# SH4_-_OPAMPS.net
KiCad netlist of a schematic drawn in Altium Designer
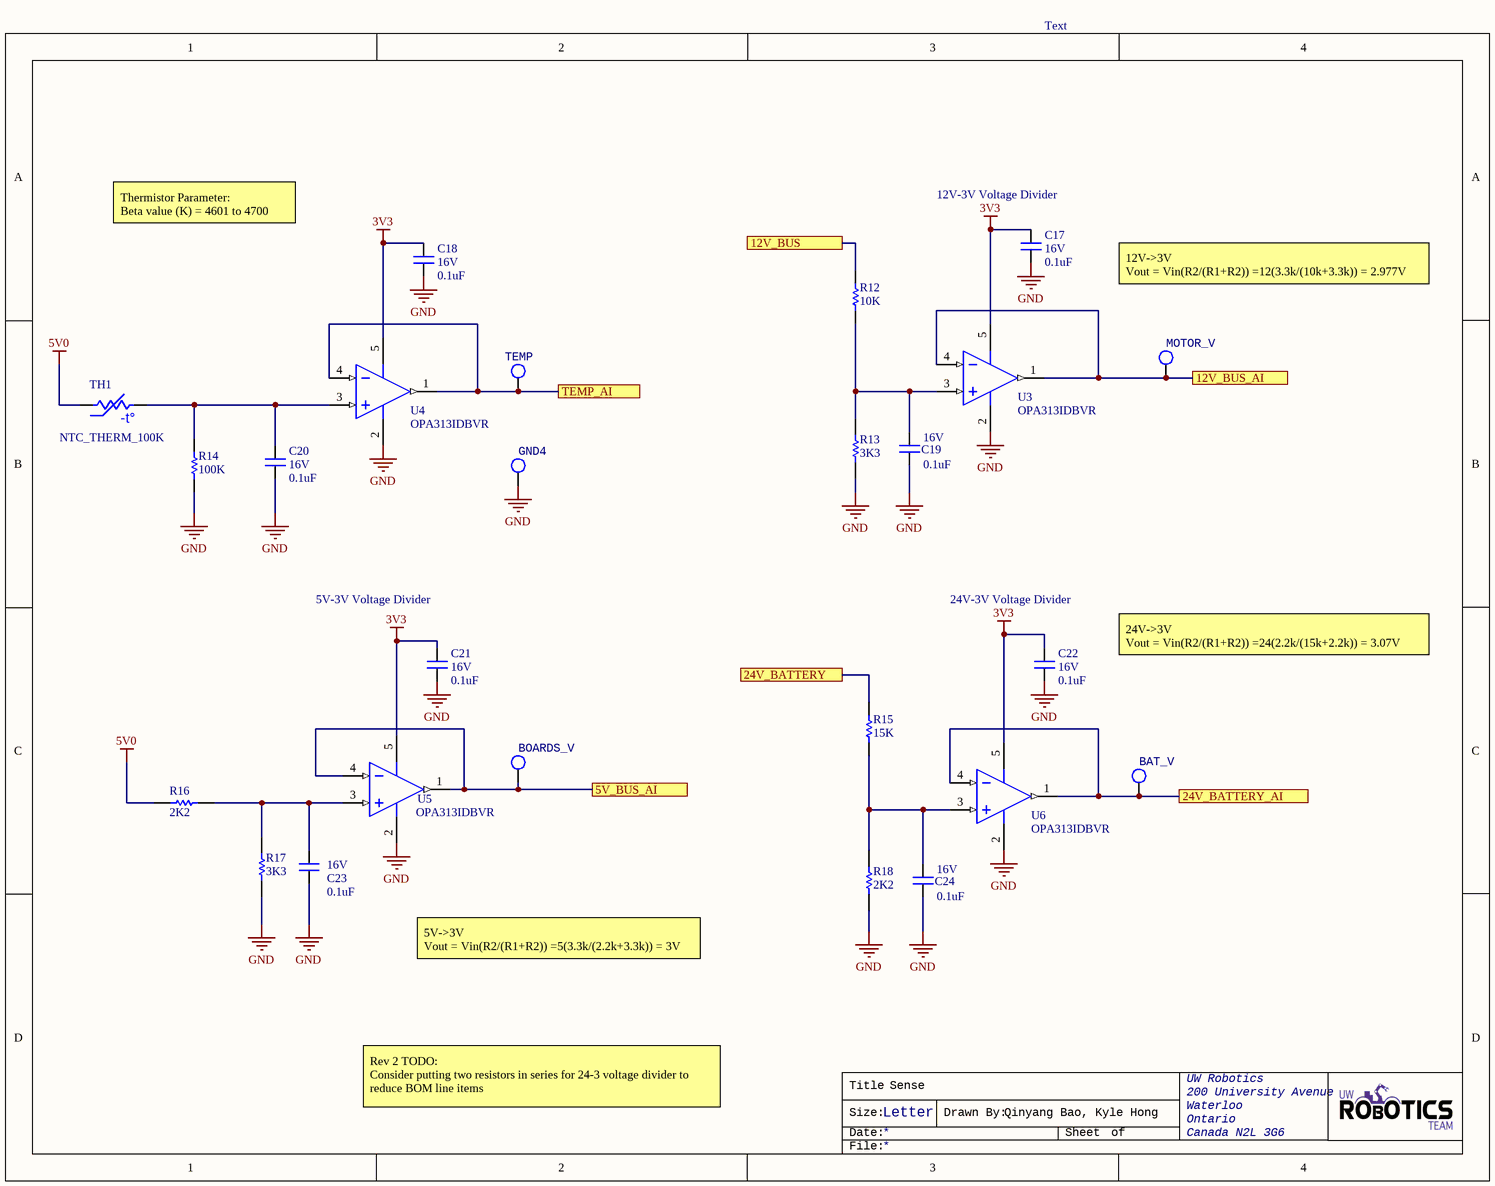
[diagram p0: SH4 - OPAMPS.SchDoc]

(export (version "E")
  (design (tool "Eeschema 10.0.6"))
  (components
    (comp (ref "BAT_V")
      (value "TESTPOINT_LOOP")
      (footprint "TESTPOINT_LOOP")
      (description "Loop testpoint through-hole pad")
      (fields (field (name "MANUFACTURER") "Keystone Electronics"))
      (libsource (lib "UWRT_Schematic_Library_2020") (part "TESTPOINT_LOOP"))
    )
    (comp (ref "BOARDS_V")
      (value "TESTPOINT_LOOP")
      (footprint "TESTPOINT_LOOP")
      (description "Loop testpoint through-hole pad")
      (fields (field (name "MANUFACTURER") "Keystone Electronics"))
      (libsource (lib "UWRT_Schematic_Library_2020") (part "TESTPOINT_LOOP"))
    )
    (comp (ref "C17")
      (value "0.1uF")
      (footprint "CAPC0603(1608)55_N")
      (description "CAP CER 0.1UF 16V X7R 0603")
      (fields
        (field (name "MPN") "CC0603KRX7R7BB104")
        (field (name "MANUFACTURER") "Yageo")
        (field (name "VOLTAGE RATING") "16V")
      )
      (libsource (lib "UWRT_Schematic_Library_2020") (part "CAP_0.1uF_16V_0603"))
    )
    (comp (ref "C18")
      (value "0.1uF")
      (footprint "CAPC0603(1608)55_N")
      (description "CAP CER 0.1UF 16V X7R 0603")
      (fields
        (field (name "MPN") "CC0603KRX7R7BB104")
        (field (name "MANUFACTURER") "Yageo")
        (field (name "VOLTAGE RATING") "16V")
      )
      (libsource (lib "UWRT_Schematic_Library_2020") (part "CAP_0.1uF_16V_0603"))
    )
    (comp (ref "C19")
      (value "0.1uF")
      (footprint "CAPC0603(1608)55_N")
      (description "CAP CER 0.1UF 16V X7R 0603")
      (fields
        (field (name "MPN") "CC0603KRX7R7BB104")
        (field (name "MANUFACTURER") "Yageo")
        (field (name "VOLTAGE RATING") "16V")
      )
      (libsource (lib "UWRT_Schematic_Library_2020") (part "CAP_0.1uF_16V_0603"))
    )
    (comp (ref "C20")
      (value "0.1uF")
      (footprint "CAPC0603(1608)55_N")
      (description "CAP CER 0.1UF 16V X7R 0603")
      (fields
        (field (name "MPN") "CC0603KRX7R7BB104")
        (field (name "MANUFACTURER") "Yageo")
        (field (name "VOLTAGE RATING") "16V")
      )
      (libsource (lib "UWRT_Schematic_Library_2020") (part "CAP_0.1uF_16V_0603"))
    )
    (comp (ref "C21")
      (value "0.1uF")
      (footprint "CAPC0603(1608)55_N")
      (description "CAP CER 0.1UF 16V X7R 0603")
      (fields
        (field (name "MPN") "CC0603KRX7R7BB104")
        (field (name "MANUFACTURER") "Yageo")
        (field (name "VOLTAGE RATING") "16V")
      )
      (libsource (lib "UWRT_Schematic_Library_2020") (part "CAP_0.1uF_16V_0603"))
    )
    (comp (ref "C22")
      (value "0.1uF")
      (footprint "CAPC0603(1608)55_N")
      (description "CAP CER 0.1UF 16V X7R 0603")
      (fields
        (field (name "MPN") "CC0603KRX7R7BB104")
        (field (name "MANUFACTURER") "Yageo")
        (field (name "VOLTAGE RATING") "16V")
      )
      (libsource (lib "UWRT_Schematic_Library_2020") (part "CAP_0.1uF_16V_0603"))
    )
    (comp (ref "C23")
      (value "0.1uF")
      (footprint "CAPC0603(1608)55_N")
      (description "CAP CER 0.1UF 16V X7R 0603")
      (fields
        (field (name "MPN") "CC0603KRX7R7BB104")
        (field (name "MANUFACTURER") "Yageo")
        (field (name "VOLTAGE RATING") "16V")
      )
      (libsource (lib "UWRT_Schematic_Library_2020") (part "CAP_0.1uF_16V_0603"))
    )
    (comp (ref "C24")
      (value "0.1uF")
      (footprint "CAPC0603(1608)55_N")
      (description "CAP CER 0.1UF 16V X7R 0603")
      (fields
        (field (name "MPN") "CC0603KRX7R7BB104")
        (field (name "MANUFACTURER") "Yageo")
        (field (name "VOLTAGE RATING") "16V")
      )
      (libsource (lib "UWRT_Schematic_Library_2020") (part "CAP_0.1uF_16V_0603"))
    )
    (comp (ref "GND4")
      (value "TESTPOINT_LOOP")
      (footprint "TESTPOINT_LOOP")
      (description "Loop testpoint through-hole pad")
      (fields (field (name "MANUFACTURER") "Keystone Electronics"))
      (libsource (lib "UWRT_Schematic_Library_2020") (part "TESTPOINT_LOOP"))
    )
    (comp (ref "MOTOR_V")
      (value "TESTPOINT_LOOP")
      (footprint "TESTPOINT_LOOP")
      (description "Loop testpoint through-hole pad")
      (fields (field (name "MANUFACTURER") "Keystone Electronics"))
      (libsource (lib "UWRT_Schematic_Library_2020") (part "TESTPOINT_LOOP"))
    )
    (comp (ref "R12")
      (value "10K")
      (footprint "RESC0603(1608)_N")
      (description "RES SMD 10K OHM 5% 1/10W 0603")
      (fields (field (name "TOLERANCE") "5%") (field (name "MANUFACTURER") "Yageo"))
      (libsource (lib "UWRT_Schematic_Library_2020") (part "RES_10K_0603"))
    )
    (comp (ref "R13")
      (value "3K3")
      (footprint "RESC0603(1608)_N")
      (description "RES SMD 3.3K OHM 5% 1/10W 0603")
      (fields (field (name "TOLERANCE") "5%") (field (name "MANUFACTURER") "Yageo"))
      (libsource (lib "UWRT_Schematic_Library_2020") (part "RES_3K3_0603"))
    )
    (comp (ref "R14")
      (value "100K")
      (footprint "RESC0603(1608)_N")
      (description "RES SMD 100K OHM 5% 1/10W 0603")
      (fields (field (name "TOLERANCE") "5%") (field (name "MANUFACTURER") "Yageo"))
      (libsource (lib "UWRT_Schematic_Library_2020") (part "RES_100K_0603"))
    )
    (comp (ref "R15")
      (value "15K")
      (footprint "RESC0603(1608)_N")
      (description "RES SMD 15K OHM 5% 1/10W 0603")
      (fields (field (name "TOLERANCE") "5%") (field (name "Comment") "RES_15K_0603"))
      (libsource (lib "UWRT_Schematic_Library_2020") (part "RES_15K_0603"))
    )
    (comp (ref "R16")
      (value "2K2")
      (footprint "RESC0603(1608)_N")
      (description "RES SMD 2.2K OHM 1% 1/10W 0603")
      (fields (field (name "TOLERANCE") "1%") (field (name "MANUFACTURER") "Yageo"))
      (libsource (lib "UWRT_Schematic_Library_2020") (part "RES_2K2_0603"))
    )
    (comp (ref "R17")
      (value "3K3")
      (footprint "RESC0603(1608)_N")
      (description "RES SMD 3.3K OHM 5% 1/10W 0603")
      (fields (field (name "TOLERANCE") "5%") (field (name "MANUFACTURER") "Yageo"))
      (libsource (lib "UWRT_Schematic_Library_2020") (part "RES_3K3_0603"))
    )
    (comp (ref "R18")
      (value "2K2")
      (footprint "RESC0603(1608)_N")
      (description "RES SMD 2.2K OHM 1% 1/10W 0603")
      (fields (field (name "TOLERANCE") "1%") (field (name "MANUFACTURER") "Yageo"))
      (libsource (lib "UWRT_Schematic_Library_2020") (part "RES_2K2_0603"))
    )
    (comp (ref "TEMP")
      (value "TESTPOINT_LOOP")
      (footprint "TESTPOINT_LOOP")
      (description "Loop testpoint through-hole pad")
      (fields (field (name "MANUFACTURER") "Keystone Electronics"))
      (libsource (lib "UWRT_Schematic_Library_2020") (part "TESTPOINT_LOOP"))
    )
    (comp (ref "TH1")
      (value "NTC_THERM_100K")
      (footprint "RESC0603(1608)_N")
      (description "THERM NTC 100KOHM 4700K 0603")
      (fields (field (name "MPN") "ERT-J1VV104J") (field (name "MANUFACTURER") "Panasonic"))
      (libsource (lib "UWRT_Schematic_Library_2020") (part "NTC_THERM_100K"))
    )
    (comp (ref "U3")
      (value "OPA313IDBVR")
      (footprint "DBV0005A_M")
      (description "IC OPAMP GP 1 CIRCUIT SOT23-5")
      (fields (field (name "MANUFACTURER") "Texas Instruments"))
      (libsource (lib "UWRT_Schematic_Library_2020") (part "OPAMP"))
    )
    (comp (ref "U4")
      (value "OPA313IDBVR")
      (footprint "DBV0005A_M")
      (description "IC OPAMP GP 1 CIRCUIT SOT23-5")
      (fields (field (name "MANUFACTURER") "Texas Instruments"))
      (libsource (lib "UWRT_Schematic_Library_2020") (part "OPAMP"))
    )
    (comp (ref "U5")
      (value "OPA313IDBVR")
      (footprint "DBV0005A_M")
      (description "IC OPAMP GP 1 CIRCUIT SOT23-5")
      (fields (field (name "MANUFACTURER") "Texas Instruments"))
      (libsource (lib "UWRT_Schematic_Library_2020") (part "OPAMP"))
    )
    (comp (ref "U6")
      (value "OPA313IDBVR")
      (footprint "DBV0005A_M")
      (description "IC OPAMP GP 1 CIRCUIT SOT23-5")
      (fields (field (name "MANUFACTURER") "Texas Instruments"))
      (libsource (lib "UWRT_Schematic_Library_2020") (part "OPAMP"))
    )
  )
  (nets
    (net (code "1") (name "/5V_BUS_AI") (class "Default")
      (node (ref "BOARDS_V") (pin "1") (pintype "passive"))
      (node (ref "U5") (pin "1") (pinfunction "OUT_1") (pintype "output"))
      (node (ref "U5") (pin "4") (pinfunction "IN-_4") (pintype "input"))
    )
    (net (code "2") (name "/12V_BUS") (class "Default")
      (node (ref "R12") (pin "2") (pinfunction "2_2") (pintype "passive"))
    )
    (net (code "3") (name "/12V_BUS_AI") (class "Default")
      (node (ref "MOTOR_V") (pin "1") (pintype "passive"))
      (node (ref "U3") (pin "1") (pinfunction "OUT_1") (pintype "output"))
      (node (ref "U3") (pin "4") (pinfunction "IN-_4") (pintype "input"))
    )
    (net (code "4") (name "/24V_BATTERY") (class "Default")
      (node (ref "R15") (pin "2") (pinfunction "2_2") (pintype "passive"))
    )
    (net (code "5") (name "/24V_BATTERY_AI") (class "Default")
      (node (ref "BAT_V") (pin "1") (pintype "passive"))
      (node (ref "U6") (pin "1") (pinfunction "OUT_1") (pintype "output"))
      (node (ref "U6") (pin "4") (pinfunction "IN-_4") (pintype "input"))
    )
    (net (code "6") (name "/TEMP_AI") (class "Default")
      (node (ref "TEMP") (pin "1") (pintype "passive"))
      (node (ref "U4") (pin "1") (pinfunction "OUT_1") (pintype "output"))
      (node (ref "U4") (pin "4") (pinfunction "IN-_4") (pintype "input"))
    )
    (net (code "7") (name "3V3") (class "Default")
      (node (ref "C17") (pin "2") (pinfunction "2_2") (pintype "passive"))
      (node (ref "C18") (pin "1") (pinfunction "1_1") (pintype "passive"))
      (node (ref "C21") (pin "2") (pinfunction "2_2") (pintype "passive"))
      (node (ref "C22") (pin "2") (pinfunction "2_2") (pintype "passive"))
      (node (ref "U3") (pin "5") (pinfunction "V+_5") (pintype "power_in"))
      (node (ref "U4") (pin "5") (pinfunction "V+_5") (pintype "power_in"))
      (node (ref "U5") (pin "5") (pinfunction "V+_5") (pintype "power_in"))
      (node (ref "U6") (pin "5") (pinfunction "V+_5") (pintype "power_in"))
    )
    (net (code "8") (name "5V0") (class "Default")
      (node (ref "R16") (pin "2") (pinfunction "2_2") (pintype "passive"))
      (node (ref "TH1") (pin "2") (pinfunction "2_2") (pintype "passive"))
    )
    (net (code "9") (name "GND") (class "Default")
      (node (ref "C17") (pin "1") (pinfunction "1_1") (pintype "passive"))
      (node (ref "C18") (pin "2") (pinfunction "2_2") (pintype "passive"))
      (node (ref "C19") (pin "1") (pinfunction "1_1") (pintype "passive"))
      (node (ref "C20") (pin "1") (pinfunction "1_1") (pintype "passive"))
      (node (ref "C21") (pin "1") (pinfunction "1_1") (pintype "passive"))
      (node (ref "C22") (pin "1") (pinfunction "1_1") (pintype "passive"))
      (node (ref "C23") (pin "1") (pinfunction "1_1") (pintype "passive"))
      (node (ref "C24") (pin "1") (pinfunction "1_1") (pintype "passive"))
      (node (ref "GND4") (pin "1") (pintype "passive"))
      (node (ref "R13") (pin "1") (pinfunction "1_1") (pintype "passive"))
      (node (ref "R14") (pin "1") (pinfunction "1_1") (pintype "passive"))
      (node (ref "R17") (pin "1") (pinfunction "1_1") (pintype "passive"))
      (node (ref "R18") (pin "1") (pinfunction "1_1") (pintype "passive"))
      (node (ref "U3") (pin "2") (pinfunction "V-_2") (pintype "power_in"))
      (node (ref "U4") (pin "2") (pinfunction "V-_2") (pintype "power_in"))
      (node (ref "U5") (pin "2") (pinfunction "V-_2") (pintype "power_in"))
      (node (ref "U6") (pin "2") (pinfunction "V-_2") (pintype "power_in"))
    )
    (net (code "10") (name "Net-(U3-IN+)") (class "Default")
      (node (ref "C19") (pin "2") (pinfunction "2_2") (pintype "passive"))
      (node (ref "R12") (pin "1") (pinfunction "1_1") (pintype "passive"))
      (node (ref "R13") (pin "2") (pinfunction "2_2") (pintype "passive"))
      (node (ref "U3") (pin "3") (pinfunction "IN+_3") (pintype "input"))
    )
    (net (code "11") (name "Net-(U4-IN+)") (class "Default")
      (node (ref "C20") (pin "2") (pinfunction "2_2") (pintype "passive"))
      (node (ref "R14") (pin "2") (pinfunction "2_2") (pintype "passive"))
      (node (ref "TH1") (pin "1") (pinfunction "1_1") (pintype "passive"))
      (node (ref "U4") (pin "3") (pinfunction "IN+_3") (pintype "input"))
    )
    (net (code "12") (name "Net-(U5-IN+)") (class "Default")
      (node (ref "C23") (pin "2") (pinfunction "2_2") (pintype "passive"))
      (node (ref "R16") (pin "1") (pinfunction "1_1") (pintype "passive"))
      (node (ref "R17") (pin "2") (pinfunction "2_2") (pintype "passive"))
      (node (ref "U5") (pin "3") (pinfunction "IN+_3") (pintype "input"))
    )
    (net (code "13") (name "Net-(U6-IN+)") (class "Default")
      (node (ref "C24") (pin "2") (pinfunction "2_2") (pintype "passive"))
      (node (ref "R15") (pin "1") (pinfunction "1_1") (pintype "passive"))
      (node (ref "R18") (pin "2") (pinfunction "2_2") (pintype "passive"))
      (node (ref "U6") (pin "3") (pinfunction "IN+_3") (pintype "input"))
    )
  )
)
